# pic18f46k22_evb.net
KiCad netlist of a schematic drawn in EAGLE
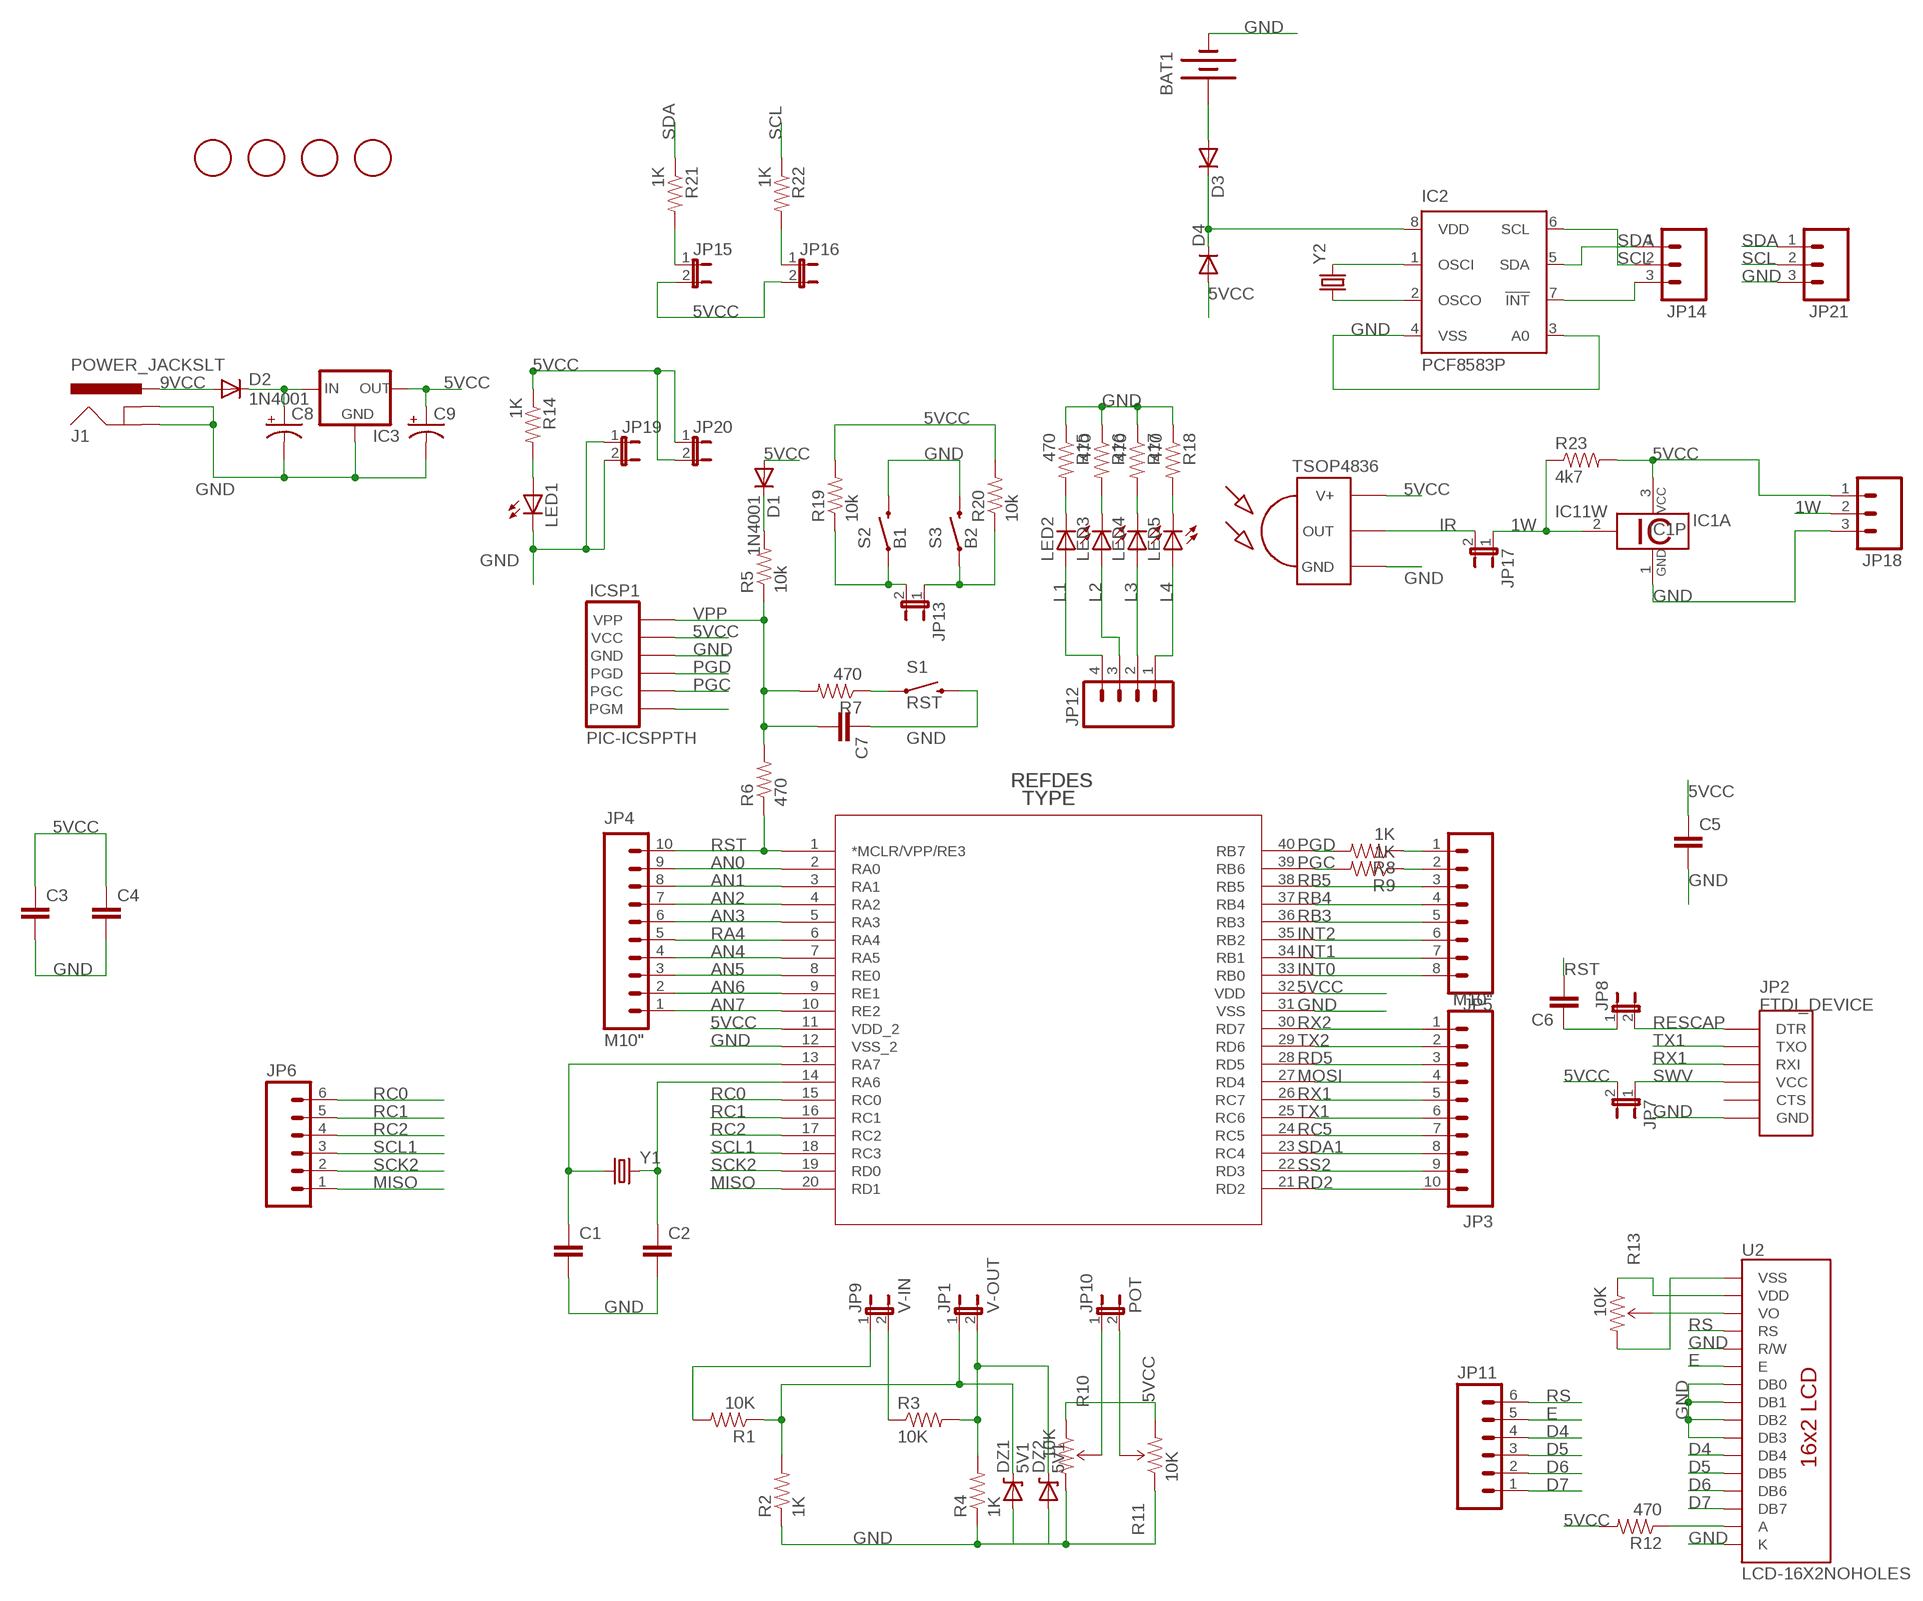
[diagram p0: schematic, sheet 1]

(export (version "E")
  (design (tool "Eeschema 10.0.6"))
  (components
    (comp (ref "BAT1")
      (value "BATTERY12MM")
      (footprint "eagle-import:BATTCON_12MM")
      (libsource (lib "eagle-import") (part "BATTERY12MM"))
    )
    (comp (ref "C1")
      (value "CAPPTH1")
      (footprint "eagle-import:CAP-PTH-5MM")
      (libsource (lib "eagle-import") (part "CAPPTH1"))
    )
    (comp (ref "C2")
      (value "CAPPTH1")
      (footprint "eagle-import:CAP-PTH-5MM")
      (libsource (lib "eagle-import") (part "CAPPTH1"))
    )
    (comp (ref "C3")
      (value "CAPPTH1")
      (footprint "eagle-import:CAP-PTH-5MM")
      (libsource (lib "eagle-import") (part "CAPPTH1"))
    )
    (comp (ref "C4")
      (value "CAPPTH1")
      (footprint "eagle-import:CAP-PTH-5MM")
      (libsource (lib "eagle-import") (part "CAPPTH1"))
    )
    (comp (ref "C5")
      (value "CAPPTH1")
      (footprint "eagle-import:CAP-PTH-5MM")
      (libsource (lib "eagle-import") (part "CAPPTH1"))
    )
    (comp (ref "C6")
      (value "CAPPTH1")
      (footprint "eagle-import:CAP-PTH-5MM")
      (libsource (lib "eagle-import") (part "CAPPTH1"))
    )
    (comp (ref "C7")
      (value "CAPPTH1")
      (footprint "eagle-import:CAP-PTH-5MM")
      (libsource (lib "eagle-import") (part "CAPPTH1"))
    )
    (comp (ref "C8")
      (value "CAP_POLPTH1")
      (footprint "eagle-import:CPOL-RADIAL-100UF-25V")
      (libsource (lib "eagle-import") (part "CAP_POLPTH1"))
    )
    (comp (ref "C9")
      (value "CAP_POLPTH2")
      (footprint "eagle-import:CPOL-RADIAL-10UF-25V")
      (libsource (lib "eagle-import") (part "CAP_POLPTH2"))
    )
    (comp (ref "D1")
      (value "1N4001")
      (footprint "eagle-import:DIODE-1N4001")
      (libsource (lib "eagle-import") (part "DIODEPTH"))
    )
    (comp (ref "D2")
      (value "1N4001")
      (footprint "eagle-import:DIODE-1N4001")
      (libsource (lib "eagle-import") (part "DIODEPTH"))
    )
    (comp (ref "D3")
      (value "DIODE1N4148")
      (footprint "eagle-import:DIODE-1N4148")
      (libsource (lib "eagle-import") (part "DIODE1N4148"))
    )
    (comp (ref "D4")
      (value "DIODE1N4148")
      (footprint "eagle-import:DIODE-1N4148")
      (libsource (lib "eagle-import") (part "DIODE1N4148"))
    )
    (comp (ref "DZ1")
      (value "5V1")
      (footprint "eagle-import:DIODE-ZENER")
      (libsource (lib "eagle-import") (part "DIODE-ZENERPTH"))
    )
    (comp (ref "DZ2")
      (value "5V1")
      (footprint "eagle-import:DIODE-ZENER")
      (libsource (lib "eagle-import") (part "DIODE-ZENERPTH"))
    )
    (comp (ref "IC1")
      (value "DS18B20")
      (footprint "eagle-import:TO92-")
      (libsource (lib "eagle-import") (part "DS18B20"))
    )
    (comp (ref "IC2")
      (value "PCF8583P")
      (footprint "eagle-import:DIL08")
      (libsource (lib "eagle-import") (part "PCF8583P"))
    )
    (comp (ref "IC3")
      (value "V_REG_78XXSINK")
      (footprint "eagle-import:TO220-IGO")
      (libsource (lib "eagle-import") (part "V_REG_78XXSINK"))
    )
    (comp (ref "ICSP1")
      (value "PIC-ICSPPTH")
      (footprint "eagle-import:MOLEX-1X6")
      (libsource (lib "eagle-import") (part "PIC-ICSPPTH"))
    )
    (comp (ref "J1")
      (value "POWER_JACKSLT")
      (footprint "eagle-import:POWER_JACK_SLOT")
      (libsource (lib "eagle-import") (part "POWER_JACKSLT"))
    )
    (comp (ref "JP1")
      (value "V-OUT")
      (footprint "eagle-import:1X02")
      (libsource (lib "eagle-import") (part "JUMPER-2PTH"))
    )
    (comp (ref "JP2")
      (value "FTDI_DEVICE")
      (footprint "eagle-import:FTDI_DEVICE_SIDE")
      (libsource (lib "eagle-import") (part "FTDI_DEVICE"))
    )
    (comp (ref "JP3")
      (value "M10\"")
      (footprint "eagle-import:1X10")
      (libsource (lib "eagle-import") (part "M10{dblquote}"))
    )
    (comp (ref "JP4")
      (value "M10\"")
      (footprint "eagle-import:1X10")
      (libsource (lib "eagle-import") (part "M10{dblquote}"))
    )
    (comp (ref "JP5")
      (value "M081X08")
      (footprint "eagle-import:1X08")
      (libsource (lib "eagle-import") (part "M081X08"))
    )
    (comp (ref "JP6")
      (value "M06SIP")
      (footprint "eagle-import:1X06")
      (libsource (lib "eagle-import") (part "M06SIP"))
    )
    (comp (ref "JP7")
      (value "JUMPER-2PTH")
      (footprint "eagle-import:1X02")
      (libsource (lib "eagle-import") (part "JUMPER-2PTH"))
    )
    (comp (ref "JP8")
      (value "JUMPER-2PTH")
      (footprint "eagle-import:1X02")
      (libsource (lib "eagle-import") (part "JUMPER-2PTH"))
    )
    (comp (ref "JP9")
      (value "V-IN")
      (footprint "eagle-import:1X02")
      (libsource (lib "eagle-import") (part "JUMPER-2PTH"))
    )
    (comp (ref "JP10")
      (value "POT")
      (footprint "eagle-import:1X02")
      (libsource (lib "eagle-import") (part "JUMPER-2PTH"))
    )
    (comp (ref "JP11")
      (value "M06SIP")
      (footprint "eagle-import:1X06")
      (libsource (lib "eagle-import") (part "M06SIP"))
    )
    (comp (ref "JP12")
      (value "M04PTH")
      (footprint "eagle-import:1X04")
      (libsource (lib "eagle-import") (part "M04PTH"))
    )
    (comp (ref "JP13")
      (value "JUMPER-2PTH")
      (footprint "eagle-import:1X02")
      (libsource (lib "eagle-import") (part "JUMPER-2PTH"))
    )
    (comp (ref "JP14")
      (value "M03PTH")
      (footprint "eagle-import:1X03")
      (libsource (lib "eagle-import") (part "M03PTH"))
    )
    (comp (ref "JP15")
      (value "JUMPER-2PTH")
      (footprint "eagle-import:1X02")
      (libsource (lib "eagle-import") (part "JUMPER-2PTH"))
    )
    (comp (ref "JP16")
      (value "JUMPER-2PTH")
      (footprint "eagle-import:1X02")
      (libsource (lib "eagle-import") (part "JUMPER-2PTH"))
    )
    (comp (ref "JP17")
      (value "JUMPER-2PTH")
      (footprint "eagle-import:1X02")
      (libsource (lib "eagle-import") (part "JUMPER-2PTH"))
    )
    (comp (ref "JP18")
      (value "M03PTH")
      (footprint "eagle-import:1X03")
      (libsource (lib "eagle-import") (part "M03PTH"))
    )
    (comp (ref "JP19")
      (value "JUMPER-2PTH")
      (footprint "eagle-import:1X02")
      (libsource (lib "eagle-import") (part "JUMPER-2PTH"))
    )
    (comp (ref "JP20")
      (value "JUMPER-2PTH")
      (footprint "eagle-import:1X02")
      (libsource (lib "eagle-import") (part "JUMPER-2PTH"))
    )
    (comp (ref "JP21")
      (value "M03PTH")
      (footprint "eagle-import:1X03")
      (libsource (lib "eagle-import") (part "M03PTH"))
    )
    (comp (ref "LED1")
      (value "LED3MM")
      (footprint "eagle-import:LED3MM")
      (libsource (lib "eagle-import") (part "LED3MM"))
    )
    (comp (ref "LED2")
      (value "LED3MM")
      (footprint "eagle-import:LED3MM")
      (libsource (lib "eagle-import") (part "LED3MM"))
    )
    (comp (ref "LED3")
      (value "LED3MM")
      (footprint "eagle-import:LED3MM")
      (libsource (lib "eagle-import") (part "LED3MM"))
    )
    (comp (ref "LED4")
      (value "LED3MM")
      (footprint "eagle-import:LED3MM")
      (libsource (lib "eagle-import") (part "LED3MM"))
    )
    (comp (ref "LED5")
      (value "LED3MM")
      (footprint "eagle-import:LED3MM")
      (libsource (lib "eagle-import") (part "LED3MM"))
    )
    (comp (ref "R1")
      (value "10K")
      (footprint "eagle-import:AXIAL-0.3")
      (libsource (lib "eagle-import") (part "RESISTORAXIAL-0.3"))
    )
    (comp (ref "R2")
      (value "1K")
      (footprint "eagle-import:AXIAL-0.3")
      (libsource (lib "eagle-import") (part "SparkFun-Resistors_RESISTORAXIAL-0.3"))
    )
    (comp (ref "R3")
      (value "10K")
      (footprint "eagle-import:AXIAL-0.3")
      (libsource (lib "eagle-import") (part "RESISTORAXIAL-0.3"))
    )
    (comp (ref "R4")
      (value "1K")
      (footprint "eagle-import:AXIAL-0.3")
      (libsource (lib "eagle-import") (part "RESISTORAXIAL-0.3"))
    )
    (comp (ref "R5")
      (value "10k")
      (footprint "eagle-import:AXIAL-0.3")
      (libsource (lib "eagle-import") (part "SparkFun-Resistors_RESISTORAXIAL-0.3"))
    )
    (comp (ref "R6")
      (value "470")
      (footprint "eagle-import:AXIAL-0.3")
      (libsource (lib "eagle-import") (part "RESISTORAXIAL-0.3"))
    )
    (comp (ref "R7")
      (value "470")
      (footprint "eagle-import:AXIAL-0.3")
      (libsource (lib "eagle-import") (part "RESISTORAXIAL-0.3"))
    )
    (comp (ref "R8")
      (value "1K")
      (footprint "eagle-import:AXIAL-0.3")
      (libsource (lib "eagle-import") (part "RESISTORAXIAL-0.3"))
    )
    (comp (ref "R9")
      (value "1K")
      (footprint "eagle-import:AXIAL-0.3")
      (libsource (lib "eagle-import") (part "RESISTORAXIAL-0.3"))
    )
    (comp (ref "R10")
      (value "10K")
      (footprint "eagle-import:TRIM_POT_PTH")
      (libsource (lib "eagle-import") (part "TRIMPOTPTH"))
    )
    (comp (ref "R11")
      (value "10K")
      (footprint "eagle-import:TRIM_POT_PTH")
      (libsource (lib "eagle-import") (part "TRIMPOTPTH"))
    )
    (comp (ref "R12")
      (value "470")
      (footprint "eagle-import:AXIAL-0.3")
      (libsource (lib "eagle-import") (part "RESISTORAXIAL-0.3"))
    )
    (comp (ref "R13")
      (value "10K")
      (footprint "eagle-import:TRIM_POT_PTH")
      (libsource (lib "eagle-import") (part "TRIMPOTPTH"))
    )
    (comp (ref "R14")
      (value "1K")
      (footprint "eagle-import:AXIAL-0.3")
      (libsource (lib "eagle-import") (part "RESISTORAXIAL-0.3"))
    )
    (comp (ref "R15")
      (value "470")
      (footprint "eagle-import:AXIAL-0.3")
      (libsource (lib "eagle-import") (part "RESISTORAXIAL-0.3"))
    )
    (comp (ref "R16")
      (value "470")
      (footprint "eagle-import:AXIAL-0.3")
      (libsource (lib "eagle-import") (part "RESISTORAXIAL-0.3"))
    )
    (comp (ref "R17")
      (value "470")
      (footprint "eagle-import:AXIAL-0.3")
      (libsource (lib "eagle-import") (part "RESISTORAXIAL-0.3"))
    )
    (comp (ref "R18")
      (value "470")
      (footprint "eagle-import:AXIAL-0.3")
      (libsource (lib "eagle-import") (part "RESISTORAXIAL-0.3"))
    )
    (comp (ref "R19")
      (value "10k")
      (footprint "eagle-import:AXIAL-0.3")
      (libsource (lib "eagle-import") (part "SparkFun-Resistors_RESISTORAXIAL-0.3"))
    )
    (comp (ref "R20")
      (value "10k")
      (footprint "eagle-import:AXIAL-0.3")
      (libsource (lib "eagle-import") (part "SparkFun-Resistors_RESISTORAXIAL-0.3"))
    )
    (comp (ref "R21")
      (value "1K")
      (footprint "eagle-import:AXIAL-0.3")
      (libsource (lib "eagle-import") (part "RESISTORAXIAL-0.3"))
    )
    (comp (ref "R22")
      (value "1K")
      (footprint "eagle-import:AXIAL-0.3")
      (libsource (lib "eagle-import") (part "RESISTORAXIAL-0.3"))
    )
    (comp (ref "R23")
      (value "4k7")
      (footprint "eagle-import:AXIAL-0.3")
      (libsource (lib "eagle-import") (part "RESISTORAXIAL-0.3"))
    )
    (comp (ref "S1")
      (value "RST")
      (footprint "eagle-import:TACTILE-PTH")
      (libsource (lib "eagle-import") (part "SWITCH-MOMENTARY-2PTH"))
    )
    (comp (ref "S2")
      (value "B1")
      (footprint "eagle-import:TACTILE-PTH")
      (libsource (lib "eagle-import") (part "SWITCH-MOMENTARY-2PTH"))
    )
    (comp (ref "S3")
      (value "B2")
      (footprint "eagle-import:TACTILE-PTH")
      (libsource (lib "eagle-import") (part "SWITCH-MOMENTARY-2PTH"))
    )
    (comp (ref "U$1")
      (value "MOUNTINGHOLE3.0THIN")
      (footprint "eagle-import:MOUNTINGHOLE_3.0_PLATEDTHIN")
      (libsource (lib "eagle-import") (part "MOUNTINGHOLE3.0THIN"))
    )
    (comp (ref "U$2")
      (value "MOUNTINGHOLE3.0THIN")
      (footprint "eagle-import:MOUNTINGHOLE_3.0_PLATEDTHIN")
      (libsource (lib "eagle-import") (part "MOUNTINGHOLE3.0THIN"))
    )
    (comp (ref "U$3")
      (value "MOUNTINGHOLE3.0THIN")
      (footprint "eagle-import:MOUNTINGHOLE_3.0_PLATEDTHIN")
      (libsource (lib "eagle-import") (part "MOUNTINGHOLE3.0THIN"))
    )
    (comp (ref "U$4")
      (value "MOUNTINGHOLE3.0THIN")
      (footprint "eagle-import:MOUNTINGHOLE_3.0_PLATEDTHIN")
      (libsource (lib "eagle-import") (part "MOUNTINGHOLE3.0THIN"))
    )
    (comp (ref "U$5")
      (value "TSOP4836")
      (footprint "eagle-import:TSOP18XX")
      (libsource (lib "eagle-import") (part "TSOP4836"))
    )
    (comp (ref "U1")
      (value "PIC18F46K22")
      (footprint "eagle-import:MICROCHIP_PDIP40_600MC")
      (libsource (lib "eagle-import") (part "MICROCHIP_PIC18F46K22-X_P"))
    )
    (comp (ref "U2")
      (value "LCD-16X2NOHOLES")
      (footprint "eagle-import:LCD-16X2_NOHOLES")
      (libsource (lib "eagle-import") (part "LCD-16X2NOHOLES"))
    )
    (comp (ref "Y1")
      (value "CRYSTALHC49UV")
      (footprint "eagle-import:HC49U-V")
      (libsource (lib "eagle-import") (part "CRYSTALHC49UV"))
    )
    (comp (ref "Y2")
      (value "CRYSTALTC38H")
      (footprint "eagle-import:TC38H")
      (libsource (lib "eagle-import") (part "CRYSTALTC38H"))
    )
  )
  (nets
    (net (code "1") (name "/1W") (class "Default")
      (node (ref "IC1") (pin "2") (pinfunction "1W_2") (pintype "power_in"))
      (node (ref "JP17") (pin "1") (pinfunction "1_1") (pintype "passive"))
      (node (ref "JP18") (pin "2") (pinfunction "2_2") (pintype "passive"))
      (node (ref "R23") (pin "P$1") (pinfunction "1_P$1") (pintype "passive"))
    )
    (net (code "2") (name "/5VCC") (class "Default")
      (node (ref "C3") (pin "1") (pinfunction "1_1") (pintype "passive"))
      (node (ref "C4") (pin "1") (pinfunction "1_1") (pintype "passive"))
      (node (ref "C5") (pin "1") (pinfunction "1_1") (pintype "passive"))
      (node (ref "C9") (pin "1") (pinfunction "+_1") (pintype "passive"))
      (node (ref "D1") (pin "A") (pinfunction "A_A") (pintype "passive"))
      (node (ref "D4") (pin "A") (pinfunction "A_A") (pintype "passive"))
      (node (ref "IC1") (pin "3") (pinfunction "VDD_3") (pintype "power_in"))
      (node (ref "IC3") (pin "OUT") (pinfunction "OUT_OUT") (pintype "output"))
      (node (ref "ICSP1") (pin "5") (pinfunction "VCC_5") (pintype "bidirectional"))
      (node (ref "JP15") (pin "2") (pinfunction "2_2") (pintype "passive"))
      (node (ref "JP16") (pin "2") (pinfunction "2_2") (pintype "passive"))
      (node (ref "JP18") (pin "1") (pinfunction "1_1") (pintype "passive"))
      (node (ref "JP20") (pin "1") (pinfunction "1_1") (pintype "passive"))
      (node (ref "JP20") (pin "2") (pinfunction "2_2") (pintype "passive"))
      (node (ref "JP7") (pin "2") (pinfunction "2_2") (pintype "passive"))
      (node (ref "R10") (pin "1") (pinfunction "CCW_1") (pintype "passive"))
      (node (ref "R11") (pin "3") (pinfunction "CW_3") (pintype "passive"))
      (node (ref "R12") (pin "P$2") (pinfunction "2_P$2") (pintype "passive"))
      (node (ref "R13") (pin "1") (pinfunction "CCW_1") (pintype "passive"))
      (node (ref "R14") (pin "P$1") (pinfunction "1_P$1") (pintype "passive"))
      (node (ref "R19") (pin "P$2") (pinfunction "2_P$2") (pintype "passive"))
      (node (ref "R20") (pin "P$2") (pinfunction "2_P$2") (pintype "passive"))
      (node (ref "R23") (pin "P$2") (pinfunction "2_P$2") (pintype "passive"))
      (node (ref "U$5") (pin "VCC") (pinfunction "V+_VCC") (pintype "bidirectional"))
      (node (ref "U1") (pin "11") (pinfunction "VDD_2_11") (pintype "passive"))
      (node (ref "U1") (pin "32") (pinfunction "VDD_32") (pintype "passive"))
      (node (ref "U2") (pin "2") (pinfunction "VDD_2") (pintype "power_in"))
    )
    (net (code "3") (name "/9VCC") (class "Default")
      (node (ref "D2") (pin "A") (pinfunction "A_A") (pintype "passive"))
      (node (ref "J1") (pin "PWR") (pinfunction "PWR_PWR") (pintype "bidirectional"))
    )
    (net (code "4") (name "/AN0") (class "Default")
      (node (ref "JP4") (pin "9") (pinfunction "9_9") (pintype "passive"))
      (node (ref "U1") (pin "2") (pinfunction "RA0_2") (pintype "passive"))
    )
    (net (code "5") (name "/AN1") (class "Default")
      (node (ref "JP4") (pin "8") (pinfunction "8_8") (pintype "passive"))
      (node (ref "U1") (pin "3") (pinfunction "RA1_3") (pintype "passive"))
    )
    (net (code "6") (name "/AN2") (class "Default")
      (node (ref "JP4") (pin "7") (pinfunction "7_7") (pintype "passive"))
      (node (ref "U1") (pin "4") (pinfunction "RA2_4") (pintype "passive"))
    )
    (net (code "7") (name "/AN3") (class "Default")
      (node (ref "JP4") (pin "6") (pinfunction "6_6") (pintype "passive"))
      (node (ref "U1") (pin "5") (pinfunction "RA3_5") (pintype "passive"))
    )
    (net (code "8") (name "/AN4") (class "Default")
      (node (ref "JP4") (pin "4") (pinfunction "4_4") (pintype "passive"))
      (node (ref "U1") (pin "7") (pinfunction "RA5_7") (pintype "passive"))
    )
    (net (code "9") (name "/AN5") (class "Default")
      (node (ref "JP4") (pin "3") (pinfunction "3_3") (pintype "passive"))
      (node (ref "U1") (pin "8") (pinfunction "RE0_8") (pintype "passive"))
    )
    (net (code "10") (name "/AN6") (class "Default")
      (node (ref "JP4") (pin "2") (pinfunction "2_2") (pintype "passive"))
      (node (ref "U1") (pin "9") (pinfunction "RE1_9") (pintype "passive"))
    )
    (net (code "11") (name "/AN7") (class "Default")
      (node (ref "JP4") (pin "1") (pinfunction "1_1") (pintype "passive"))
      (node (ref "U1") (pin "10") (pinfunction "RE2_10") (pintype "passive"))
    )
    (net (code "12") (name "/D4") (class "Default")
      (node (ref "JP11") (pin "4") (pinfunction "4_4") (pintype "passive"))
      (node (ref "U2") (pin "11") (pinfunction "DB4_11") (pintype "bidirectional"))
    )
    (net (code "13") (name "/D5") (class "Default")
      (node (ref "JP11") (pin "3") (pinfunction "3_3") (pintype "passive"))
      (node (ref "U2") (pin "12") (pinfunction "DB5_12") (pintype "bidirectional"))
    )
    (net (code "14") (name "/D6") (class "Default")
      (node (ref "JP11") (pin "2") (pinfunction "2_2") (pintype "passive"))
      (node (ref "U2") (pin "13") (pinfunction "DB6_13") (pintype "bidirectional"))
    )
    (net (code "15") (name "/D7") (class "Default")
      (node (ref "JP11") (pin "1") (pinfunction "1_1") (pintype "passive"))
      (node (ref "U2") (pin "14") (pinfunction "DB7_14") (pintype "bidirectional"))
    )
    (net (code "16") (name "/E") (class "Default")
      (node (ref "JP11") (pin "5") (pinfunction "5_5") (pintype "passive"))
      (node (ref "U2") (pin "6") (pinfunction "E_6") (pintype "input"))
    )
    (net (code "17") (name "/GND") (class "Default")
      (node (ref "BAT1") (pin "GND") (pinfunction "-_GND") (pintype "power_in"))
      (node (ref "C1") (pin "2") (pinfunction "2_2") (pintype "passive"))
      (node (ref "C2") (pin "2") (pinfunction "2_2") (pintype "passive"))
      (node (ref "C3") (pin "2") (pinfunction "2_2") (pintype "passive"))
      (node (ref "C4") (pin "2") (pinfunction "2_2") (pintype "passive"))
      (node (ref "C5") (pin "2") (pinfunction "2_2") (pintype "passive"))
      (node (ref "C7") (pin "1") (pinfunction "1_1") (pintype "passive"))
      (node (ref "C8") (pin "2") (pinfunction "-_2") (pintype "passive"))
      (node (ref "C9") (pin "2") (pinfunction "-_2") (pintype "passive"))
      (node (ref "DZ1") (pin "P$2") (pinfunction "A_P$2") (pintype "passive"))
      (node (ref "DZ2") (pin "P$2") (pinfunction "A_P$2") (pintype "passive"))
      (node (ref "IC1") (pin "1") (pinfunction "GND_1") (pintype "power_in"))
      (node (ref "IC2") (pin "3") (pinfunction "A0_3") (pintype "input"))
      (node (ref "IC2") (pin "4") (pinfunction "VSS_4") (pintype "power_in"))
      (node (ref "IC3") (pin "GND") (pinfunction "GND_GND") (pintype "input"))
      (node (ref "ICSP1") (pin "4") (pinfunction "GND_4") (pintype "bidirectional"))
      (node (ref "J1") (pin "GND@1") (pinfunction "GNDBREAK_GND@1") (pintype "bidirectional"))
      (node (ref "J1") (pin "GND@2") (pinfunction "GND_GND@2") (pintype "bidirectional"))
      (node (ref "JP18") (pin "3") (pinfunction "3_3") (pintype "passive"))
      (node (ref "JP19") (pin "1") (pinfunction "1_1") (pintype "passive"))
      (node (ref "JP19") (pin "2") (pinfunction "2_2") (pintype "passive"))
      (node (ref "JP2") (pin "P$6") (pinfunction "GND_P$6") (pintype "bidirectional"))
      (node (ref "JP21") (pin "3") (pinfunction "3_3") (pintype "passive"))
      (node (ref "LED1") (pin "K") (pinfunction "C_K") (pintype "passive"))
      (node (ref "R10") (pin "3") (pinfunction "CW_3") (pintype "passive"))
      (node (ref "R11") (pin "1") (pinfunction "CCW_1") (pintype "passive"))
      (node (ref "R13") (pin "3") (pinfunction "CW_3") (pintype "passive"))
      (node (ref "R15") (pin "P$1") (pinfunction "1_P$1") (pintype "passive"))
      (node (ref "R16") (pin "P$1") (pinfunction "1_P$1") (pintype "passive"))
      (node (ref "R17") (pin "P$1") (pinfunction "1_P$1") (pintype "passive"))
      (node (ref "R18") (pin "P$1") (pinfunction "1_P$1") (pintype "passive"))
      (node (ref "R2") (pin "P$1") (pinfunction "1_P$1") (pintype "passive"))
      (node (ref "R4") (pin "P$1") (pinfunction "1_P$1") (pintype "passive"))
      (node (ref "S1") (pin "3") (pinfunction "2_3") (pintype "passive"))
      (node (ref "S2") (pin "3") (pinfunction "2_3") (pintype "passive"))
      (node (ref "S3") (pin "3") (pinfunction "2_3") (pintype "passive"))
      (node (ref "U$5") (pin "GND") (pinfunction "GND_GND") (pintype "bidirectional"))
      (node (ref "U1") (pin "12") (pinfunction "VSS_2_12") (pintype "passive"))
      (node (ref "U1") (pin "31") (pinfunction "VSS_31") (pintype "passive"))
      (node (ref "U2") (pin "1") (pinfunction "VSS_1") (pintype "power_in"))
      (node (ref "U2") (pin "10") (pinfunction "DB3_10") (pintype "bidirectional"))
      (node (ref "U2") (pin "16") (pinfunction "K_16") (pintype "power_in"))
      (node (ref "U2") (pin "5") (pinfunction "R/W_5") (pintype "input"))
      (node (ref "U2") (pin "7") (pinfunction "DB0_7") (pintype "bidirectional"))
      (node (ref "U2") (pin "8") (pinfunction "DB1_8") (pintype "bidirectional"))
      (node (ref "U2") (pin "9") (pinfunction "DB2_9") (pintype "bidirectional"))
    )
    (net (code "18") (name "/INT0") (class "Default")
      (node (ref "JP5") (pin "8") (pinfunction "8_8") (pintype "passive"))
      (node (ref "U1") (pin "33") (pinfunction "RB0_33") (pintype "passive"))
    )
    (net (code "19") (name "/INT1") (class "Default")
      (node (ref "JP5") (pin "7") (pinfunction "7_7") (pintype "passive"))
      (node (ref "U1") (pin "34") (pinfunction "RB1_34") (pintype "passive"))
    )
    (net (code "20") (name "/INT2") (class "Default")
      (node (ref "JP5") (pin "6") (pinfunction "6_6") (pintype "passive"))
      (node (ref "U1") (pin "35") (pinfunction "RB2_35") (pintype "passive"))
    )
    (net (code "21") (name "/IR") (class "Default")
      (node (ref "JP17") (pin "2") (pinfunction "2_2") (pintype "passive"))
      (node (ref "U$5") (pin "OUT") (pinfunction "OUT_OUT") (pintype "bidirectional"))
    )
    (net (code "22") (name "/L1") (class "Default")
      (node (ref "JP12") (pin "4") (pinfunction "4_4") (pintype "passive"))
      (node (ref "LED2") (pin "A") (pinfunction "A_A") (pintype "passive"))
    )
    (net (code "23") (name "/L2") (class "Default")
      (node (ref "JP12") (pin "3") (pinfunction "3_3") (pintype "passive"))
      (node (ref "LED3") (pin "A") (pinfunction "A_A") (pintype "passive"))
    )
    (net (code "24") (name "/L3") (class "Default")
      (node (ref "JP12") (pin "2") (pinfunction "2_2") (pintype "passive"))
      (node (ref "LED4") (pin "A") (pinfunction "A_A") (pintype "passive"))
    )
    (net (code "25") (name "/L4") (class "Default")
      (node (ref "JP12") (pin "1") (pinfunction "1_1") (pintype "passive"))
      (node (ref "LED5") (pin "A") (pinfunction "A_A") (pintype "passive"))
    )
    (net (code "26") (name "/MISO") (class "Default")
      (node (ref "JP6") (pin "1") (pinfunction "1_1") (pintype "passive"))
      (node (ref "U1") (pin "20") (pinfunction "RD1_20") (pintype "passive"))
    )
    (net (code "27") (name "/MOSI") (class "Default")
      (node (ref "JP3") (pin "4") (pinfunction "4_4") (pintype "passive"))
      (node (ref "U1") (pin "27") (pinfunction "RD4_27") (pintype "passive"))
    )
    (net (code "28") (name "/PGC") (class "Default")
      (node (ref "ICSP1") (pin "2") (pinfunction "PGC_2") (pintype "bidirectional"))
      (node (ref "R9") (pin "P$2") (pinfunction "2_P$2") (pintype "passive"))
      (node (ref "U1") (pin "39") (pinfunction "RB6_39") (pintype "passive"))
    )
    (net (code "29") (name "/PGD") (class "Default")
      (node (ref "ICSP1") (pin "3") (pinfunction "PGD_3") (pintype "bidirectional"))
      (node (ref "R8") (pin "P$2") (pinfunction "2_P$2") (pintype "passive"))
      (node (ref "U1") (pin "40") (pinfunction "RB7_40") (pintype "passive"))
    )
    (net (code "30") (name "/RA4") (class "Default")
      (node (ref "JP4") (pin "5") (pinfunction "5_5") (pintype "passive"))
      (node (ref "U1") (pin "6") (pinfunction "RA4_6") (pintype "passive"))
    )
    (net (code "31") (name "/RB3") (class "Default")
      (node (ref "JP5") (pin "5") (pinfunction "5_5") (pintype "passive"))
      (node (ref "U1") (pin "36") (pinfunction "RB3_36") (pintype "passive"))
    )
    (net (code "32") (name "/RB4") (class "Default")
      (node (ref "JP5") (pin "4") (pinfunction "4_4") (pintype "passive"))
      (node (ref "U1") (pin "37") (pinfunction "RB4_37") (pintype "passive"))
    )
    (net (code "33") (name "/RB5") (class "Default")
      (node (ref "JP5") (pin "3") (pinfunction "3_3") (pintype "passive"))
      (node (ref "U1") (pin "38") (pinfunction "RB5_38") (pintype "passive"))
    )
    (net (code "34") (name "/RC0") (class "Default")
      (node (ref "JP6") (pin "6") (pinfunction "6_6") (pintype "passive"))
      (node (ref "U1") (pin "15") (pinfunction "RC0_15") (pintype "passive"))
    )
    (net (code "35") (name "/RC1") (class "Default")
      (node (ref "JP6") (pin "5") (pinfunction "5_5") (pintype "passive"))
      (node (ref "U1") (pin "16") (pinfunction "RC1_16") (pintype "passive"))
    )
    (net (code "36") (name "/RC2") (class "Default")
      (node (ref "JP6") (pin "4") (pinfunction "4_4") (pintype "passive"))
      (node (ref "U1") (pin "17") (pinfunction "RC2_17") (pintype "passive"))
    )
    (net (code "37") (name "/RC5") (class "Default")
      (node (ref "JP3") (pin "7") (pinfunction "7_7") (pintype "passive"))
      (node (ref "U1") (pin "24") (pinfunction "RC5_24") (pintype "passive"))
    )
    (net (code "38") (name "/RD2") (class "Default")
      (node (ref "JP3") (pin "10") (pinfunction "10_10") (pintype "passive"))
      (node (ref "U1") (pin "21") (pinfunction "RD2_21") (pintype "passive"))
    )
    (net (code "39") (name "/RD5") (class "Default")
      (node (ref "JP3") (pin "3") (pinfunction "3_3") (pintype "passive"))
      (node (ref "U1") (pin "28") (pinfunction "RD5_28") (pintype "passive"))
    )
    (net (code "40") (name "/RESCAP") (class "Default")
      (node (ref "JP2") (pin "P$1") (pinfunction "DTR_P$1") (pintype "bidirectional"))
      (node (ref "JP8") (pin "2") (pinfunction "2_2") (pintype "passive"))
    )
    (net (code "41") (name "/RS") (class "Default")
      (node (ref "JP11") (pin "6") (pinfunction "6_6") (pintype "passive"))
      (node (ref "U2") (pin "4") (pinfunction "RS_4") (pintype "input"))
    )
    (net (code "42") (name "/RST") (class "Default")
      (node (ref "C6") (pin "2") (pinfunction "2_2") (pintype "passive"))
      (node (ref "JP4") (pin "10") (pinfunction "10_10") (pintype "passive"))
      (node (ref "R6") (pin "P$1") (pinfunction "1_P$1") (pintype "passive"))
      (node (ref "U1") (pin "1") (pinfunction "*MCLR/VPP/RE3_1") (pintype "passive"))
    )
    (net (code "43") (name "/RX1") (class "Default")
      (node (ref "JP2") (pin "P$3") (pinfunction "RXI_P$3") (pintype "bidirectional"))
      (node (ref "JP3") (pin "5") (pinfunction "5_5") (pintype "passive"))
      (node (ref "U1") (pin "26") (pinfunction "RC7_26") (pintype "passive"))
    )
    (net (code "44") (name "/RX2") (class "Default")
      (node (ref "JP3") (pin "1") (pinfunction "1_1") (pintype "passive"))
      (node (ref "U1") (pin "30") (pinfunction "RD7_30") (pintype "passive"))
    )
    (net (code "45") (name "/SCK2") (class "Default")
      (node (ref "JP6") (pin "2") (pinfunction "2_2") (pintype "passive"))
      (node (ref "U1") (pin "19") (pinfunction "RD0_19") (pintype "passive"))
    )
    (net (code "46") (name "/SCL") (class "Default")
      (node (ref "IC2") (pin "6") (pinfunction "SCL_6") (pintype "input"))
      (node (ref "JP14") (pin "2") (pinfunction "2_2") (pintype "passive"))
      (node (ref "JP21") (pin "2") (pinfunction "2_2") (pintype "passive"))
      (node (ref "R22") (pin "P$1") (pinfunction "1_P$1") (pintype "passive"))
    )
    (net (code "47") (name "/SCL1") (class "Default")
      (node (ref "JP6") (pin "3") (pinfunction "3_3") (pintype "passive"))
      (node (ref "U1") (pin "18") (pinfunction "RC3_18") (pintype "passive"))
    )
    (net (code "48") (name "/SDA") (class "Default")
      (node (ref "IC2") (pin "5") (pinfunction "SDA_5") (pintype "bidirectional"))
      (node (ref "JP14") (pin "1") (pinfunction "1_1") (pintype "passive"))
      (node (ref "JP21") (pin "1") (pinfunction "1_1") (pintype "passive"))
      (node (ref "R21") (pin "P$1") (pinfunction "1_P$1") (pintype "passive"))
    )
    (net (code "49") (name "/SDA1") (class "Default")
      (node (ref "JP3") (pin "8") (pinfunction "8_8") (pintype "passive"))
      (node (ref "U1") (pin "23") (pinfunction "RC4_23") (pintype "passive"))
    )
    (net (code "50") (name "/SS2") (class "Default")
      (node (ref "JP3") (pin "9") (pinfunction "9_9") (pintype "passive"))
      (node (ref "U1") (pin "22") (pinfunction "RD3_22") (pintype "passive"))
    )
    (net (code "51") (name "/SWV") (class "Default")
      (node (ref "JP2") (pin "P$4") (pinfunction "VCC_P$4") (pintype "bidirectional"))
      (node (ref "JP7") (pin "1") (pinfunction "1_1") (pintype "passive"))
    )
    (net (code "52") (name "/TX1") (class "Default")
      (node (ref "JP2") (pin "P$2") (pinfunction "TXO_P$2") (pintype "bidirectional"))
      (node (ref "JP3") (pin "6") (pinfunction "6_6") (pintype "passive"))
      (node (ref "U1") (pin "25") (pinfunction "RC6_25") (pintype "passive"))
    )
    (net (code "53") (name "/TX2") (class "Default")
      (node (ref "JP3") (pin "2") (pinfunction "2_2") (pintype "passive"))
      (node (ref "U1") (pin "29") (pinfunction "RD6_29") (pintype "passive"))
    )
    (net (code "54") (name "/VPP") (class "Default")
      (node (ref "C7") (pin "2") (pinfunction "2_2") (pintype "passive"))
      (node (ref "ICSP1") (pin "6") (pinfunction "VPP_6") (pintype "bidirectional"))
      (node (ref "R5") (pin "P$1") (pinfunction "1_P$1") (pintype "passive"))
      (node (ref "R6") (pin "P$2") (pinfunction "2_P$2") (pintype "passive"))
      (node (ref "R7") (pin "P$2") (pinfunction "2_P$2") (pintype "passive"))
    )
    (net (code "55") (name "Net-(BAT1-+)") (class "Default")
      (node (ref "BAT1") (pin "PWR@1") (pinfunction "+_PWR@1") (pintype "power_in"))
      (node (ref "D3") (pin "A") (pinfunction "A_A") (pintype "passive"))
    )
    (net (code "56") (name "Net-(C6-Pad1)") (class "Default")
      (node (ref "C6") (pin "1") (pinfunction "1_1") (pintype "passive"))
      (node (ref "JP8") (pin "1") (pinfunction "1_1") (pintype "passive"))
    )
    (net (code "57") (name "Net-(C8-+)") (class "Default")
      (node (ref "C8") (pin "1") (pinfunction "+_1") (pintype "passive"))
      (node (ref "D2") (pin "C") (pinfunction "C_C") (pintype "passive"))
      (node (ref "IC3") (pin "IN") (pinfunction "IN_IN") (pintype "input"))
    )
    (net (code "58") (name "Net-(DZ1-C)") (class "Default")
      (node (ref "DZ1") (pin "P$1") (pinfunction "C_P$1") (pintype "passive"))
      (node (ref "JP1") (pin "1") (pinfunction "1_1") (pintype "passive"))
      (node (ref "R1") (pin "P$1") (pinfunction "1_P$1") (pintype "passive"))
      (node (ref "R2") (pin "P$2") (pinfunction "2_P$2") (pintype "passive"))
    )
    (net (code "59") (name "Net-(DZ2-C)") (class "Default")
      (node (ref "DZ2") (pin "P$1") (pinfunction "C_P$1") (pintype "passive"))
      (node (ref "JP1") (pin "2") (pinfunction "2_2") (pintype "passive"))
      (node (ref "R3") (pin "P$2") (pinfunction "2_P$2") (pintype "passive"))
      (node (ref "R4") (pin "P$2") (pinfunction "2_P$2") (pintype "passive"))
    )
    (net (code "60") (name "Net-(IC2-OSCI)") (class "Default")
      (node (ref "IC2") (pin "1") (pinfunction "OSCI_1") (pintype "input"))
      (node (ref "Y2") (pin "2") (pinfunction "2_2") (pintype "passive"))
    )
    (net (code "61") (name "Net-(IC2-OSCO)") (class "Default")
      (node (ref "IC2") (pin "2") (pinfunction "OSCO_2") (pintype "output"))
      (node (ref "Y2") (pin "1") (pinfunction "1_1") (pintype "passive"))
    )
    (net (code "62") (name "Net-(IC2-VDD)") (class "Default")
      (node (ref "D3") (pin "C") (pinfunction "C_C") (pintype "passive"))
      (node (ref "D4") (pin "C") (pinfunction "C_C") (pintype "passive"))
      (node (ref "IC2") (pin "8") (pinfunction "VDD_8") (pintype "power_in"))
    )
    (net (code "63") (name "Net-(IC2-~{INT})") (class "Default")
      (node (ref "IC2") (pin "7") (pinfunction "~{INT}_7") (pintype "open_collector"))
      (node (ref "JP14") (pin "3") (pinfunction "3_3") (pintype "passive"))
    )
    (net (code "64") (name "Net-(LED2-C)") (class "Default")
      (node (ref "LED2") (pin "K") (pinfunction "C_K") (pintype "passive"))
      (node (ref "R15") (pin "P$2") (pinfunction "2_P$2") (pintype "passive"))
    )
    (net (code "65") (name "Net-(LED3-C)") (class "Default")
      (node (ref "LED3") (pin "K") (pinfunction "C_K") (pintype "passive"))
      (node (ref "R16") (pin "P$2") (pinfunction "2_P$2") (pintype "passive"))
    )
    (net (code "66") (name "Net-(LED4-C)") (class "Default")
      (node (ref "LED4") (pin "K") (pinfunction "C_K") (pintype "passive"))
      (node (ref "R17") (pin "P$2") (pinfunction "2_P$2") (pintype "passive"))
    )
    (net (code "67") (name "Net-(LED5-C)") (class "Default")
      (node (ref "LED5") (pin "K") (pinfunction "C_K") (pintype "passive"))
      (node (ref "R18") (pin "P$2") (pinfunction "2_P$2") (pintype "passive"))
    )
    (net (code "68") (name "Net-(R1-2)") (class "Default")
      (node (ref "JP9") (pin "1") (pinfunction "1_1") (pintype "passive"))
      (node (ref "R1") (pin "P$2") (pinfunction "2_P$2") (pintype "passive"))
    )
    (net (code "69") (name "Net-(R3-1)") (class "Default")
      (node (ref "JP9") (pin "2") (pinfunction "2_2") (pintype "passive"))
      (node (ref "R3") (pin "P$1") (pinfunction "1_P$1") (pintype "passive"))
    )
    (net (code "70") (name "Net-(R5-2)") (class "Default")
      (node (ref "D1") (pin "C") (pinfunction "C_C") (pintype "passive"))
      (node (ref "R5") (pin "P$2") (pinfunction "2_P$2") (pintype "passive"))
    )
    (net (code "71") (name "Net-(R7-1)") (class "Default")
      (node (ref "R7") (pin "P$1") (pinfunction "1_P$1") (pintype "passive"))
      (node (ref "S1") (pin "1") (pinfunction "1_1") (pintype "passive"))
    )
    (net (code "72") (name "Net-(R8-1)") (class "Default")
      (node (ref "JP5") (pin "1") (pinfunction "1_1") (pintype "passive"))
      (node (ref "R8") (pin "P$1") (pinfunction "1_P$1") (pintype "passive"))
    )
    (net (code "73") (name "Net-(R9-1)") (class "Default")
      (node (ref "JP5") (pin "2") (pinfunction "2_2") (pintype "passive"))
      (node (ref "R9") (pin "P$1") (pinfunction "1_P$1") (pintype "passive"))
    )
    (net (code "74") (name "Net-(R10-WIPER)") (class "Default")
      (node (ref "JP10") (pin "1") (pinfunction "1_1") (pintype "passive"))
      (node (ref "R10") (pin "2") (pinfunction "WIPER_2") (pintype "passive"))
    )
    (net (code "75") (name "Net-(R11-WIPER)") (class "Default")
      (node (ref "JP10") (pin "2") (pinfunction "2_2") (pintype "passive"))
      (node (ref "R11") (pin "2") (pinfunction "WIPER_2") (pintype "passive"))
    )
    (net (code "76") (name "Net-(R12-1)") (class "Default")
      (node (ref "R12") (pin "P$1") (pinfunction "1_P$1") (pintype "passive"))
      (node (ref "U2") (pin "15") (pinfunction "A_15") (pintype "power_in"))
    )
    (net (code "77") (name "Net-(R13-WIPER)") (class "Default")
      (node (ref "R13") (pin "2") (pinfunction "WIPER_2") (pintype "passive"))
      (node (ref "U2") (pin "3") (pinfunction "VO_3") (pintype "bidirectional"))
    )
    (net (code "78") (name "Net-(R14-2)") (class "Default")
      (node (ref "LED1") (pin "A") (pinfunction "A_A") (pintype "passive"))
      (node (ref "R14") (pin "P$2") (pinfunction "2_P$2") (pintype "passive"))
    )
    (net (code "79") (name "Net-(R19-1)") (class "Default")
      (node (ref "JP13") (pin "2") (pinfunction "2_2") (pintype "passive"))
      (node (ref "R19") (pin "P$1") (pinfunction "1_P$1") (pintype "passive"))
      (node (ref "S2") (pin "1") (pinfunction "1_1") (pintype "passive"))
    )
    (net (code "80") (name "Net-(R20-1)") (class "Default")
      (node (ref "JP13") (pin "1") (pinfunction "1_1") (pintype "passive"))
      (node (ref "R20") (pin "P$1") (pinfunction "1_P$1") (pintype "passive"))
      (node (ref "S3") (pin "1") (pinfunction "1_1") (pintype "passive"))
    )
    (net (code "81") (name "Net-(R21-2)") (class "Default")
      (node (ref "JP15") (pin "1") (pinfunction "1_1") (pintype "passive"))
      (node (ref "R21") (pin "P$2") (pinfunction "2_P$2") (pintype "passive"))
    )
    (net (code "82") (name "Net-(R22-2)") (class "Default")
      (node (ref "JP16") (pin "1") (pinfunction "1_1") (pintype "passive"))
      (node (ref "R22") (pin "P$2") (pinfunction "2_P$2") (pintype "passive"))
    )
    (net (code "83") (name "Net-(U1-RA6)") (class "Default")
      (node (ref "C2") (pin "1") (pinfunction "1_1") (pintype "passive"))
      (node (ref "U1") (pin "14") (pinfunction "RA6_14") (pintype "passive"))
      (node (ref "Y1") (pin "2") (pinfunction "2_2") (pintype "passive"))
    )
    (net (code "84") (name "Net-(U1-RA7)") (class "Default")
      (node (ref "C1") (pin "1") (pinfunction "1_1") (pintype "passive"))
      (node (ref "U1") (pin "13") (pinfunction "RA7_13") (pintype "passive"))
      (node (ref "Y1") (pin "1") (pinfunction "1_1") (pintype "passive"))
    )
    (net (code "85") (name "unconnected-(ICSP1-PGM-Pad1)") (class "Default")
      (node (ref "ICSP1") (pin "1") (pinfunction "PGM_1") (pintype "bidirectional"))
    )
    (net (code "86") (name "unconnected-(JP2-CTS-PadP$5)") (class "Default")
      (node (ref "JP2") (pin "P$5") (pinfunction "CTS_P$5") (pintype "bidirectional"))
    )
  )
)
